# routed_anemo4.net
KiCad netlist of a schematic drawn in EAGLE
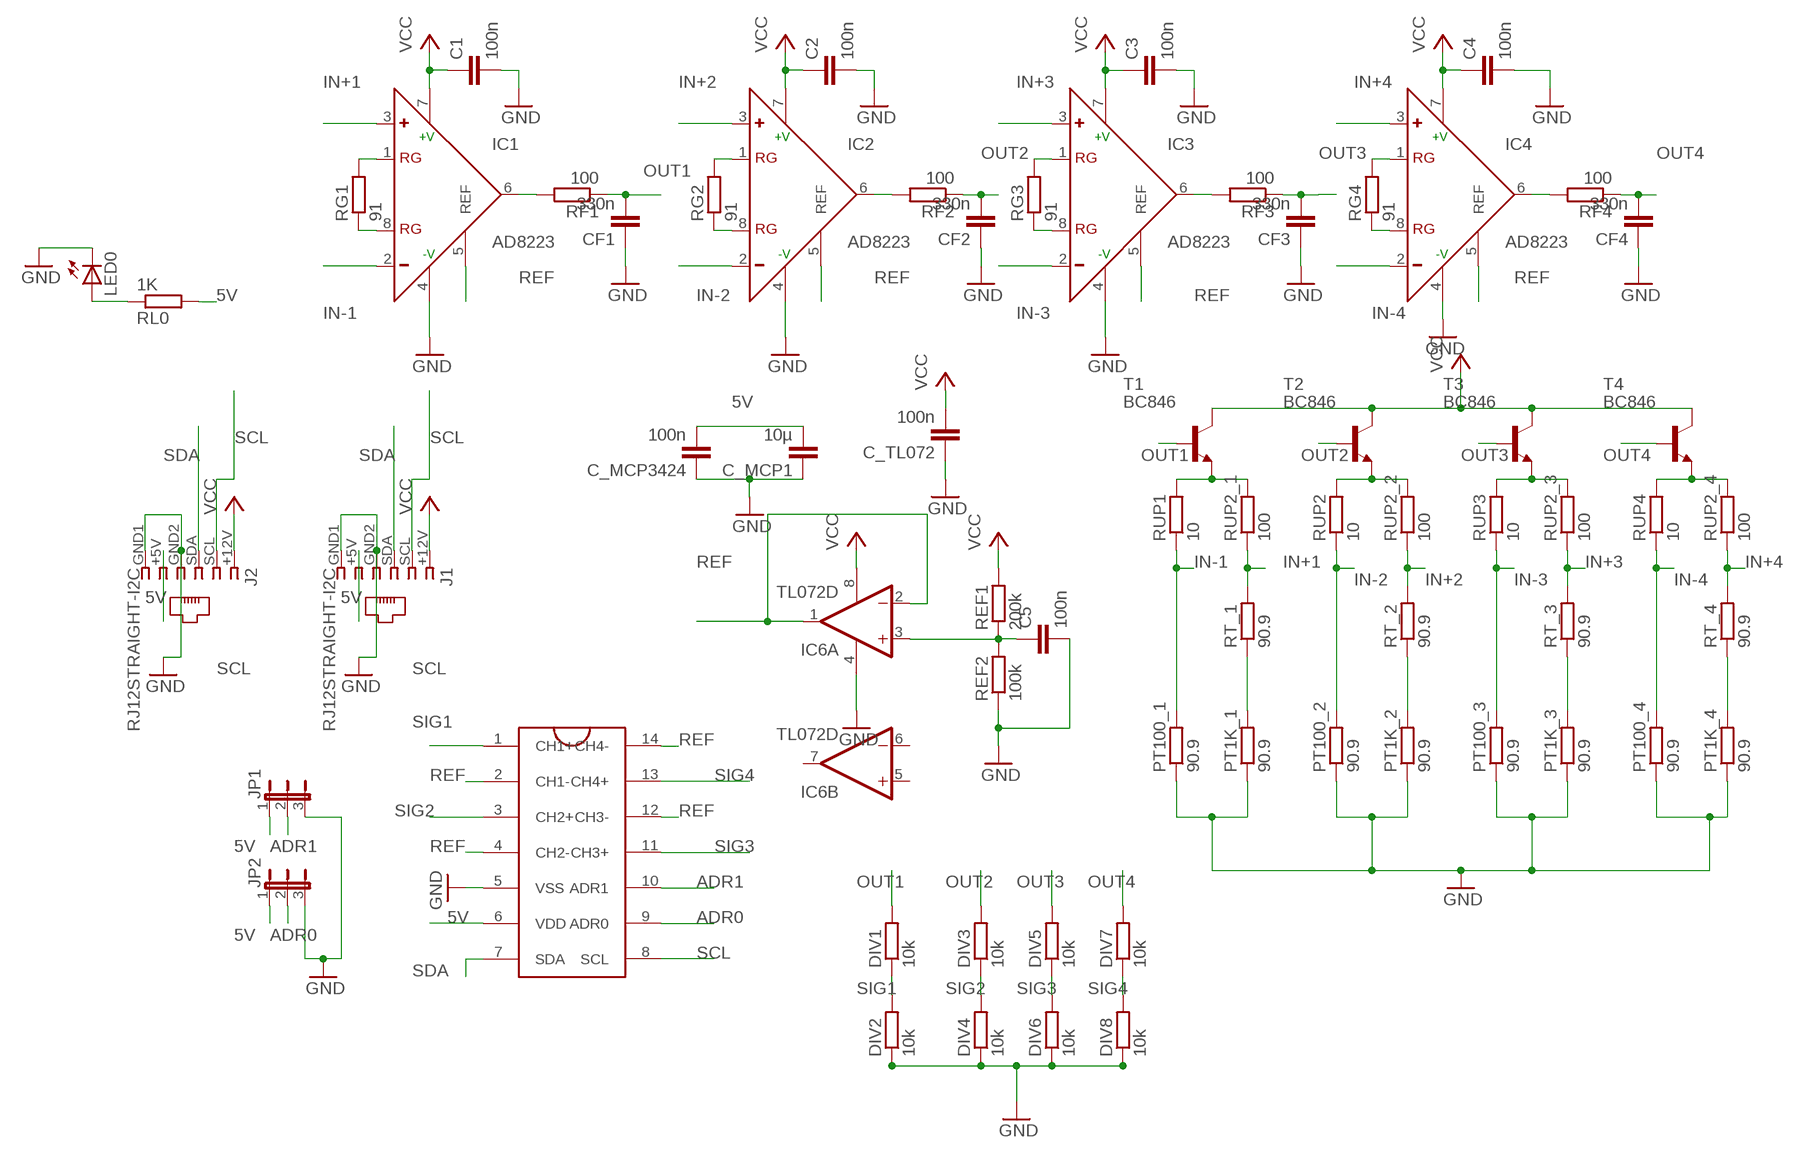
[diagram p0: schematic, sheet 1]

(export (version "E")
  (design (tool "Eeschema 10.0.6"))
  (components
    (comp (ref "C1")
      (value "100n")
      (footprint "eagle-import:C1206")
      (libsource (lib "eagle-import") (part "C-EUC1206"))
    )
    (comp (ref "C2")
      (value "100n")
      (footprint "eagle-import:C1206")
      (libsource (lib "eagle-import") (part "C-EUC1206"))
    )
    (comp (ref "C3")
      (value "100n")
      (footprint "eagle-import:C1206")
      (libsource (lib "eagle-import") (part "C-EUC1206"))
    )
    (comp (ref "C4")
      (value "100n")
      (footprint "eagle-import:C1206")
      (libsource (lib "eagle-import") (part "C-EUC1206"))
    )
    (comp (ref "C5")
      (value "100n")
      (footprint "eagle-import:C1206")
      (libsource (lib "eagle-import") (part "C-EUC1206"))
    )
    (comp (ref "CF1")
      (value "330n")
      (footprint "eagle-import:C1206")
      (libsource (lib "eagle-import") (part "C-EUC1206"))
    )
    (comp (ref "CF2")
      (value "330n")
      (footprint "eagle-import:C1206")
      (libsource (lib "eagle-import") (part "C-EUC1206"))
    )
    (comp (ref "CF3")
      (value "330n")
      (footprint "eagle-import:C1206")
      (libsource (lib "eagle-import") (part "C-EUC1206"))
    )
    (comp (ref "CF4")
      (value "330n")
      (footprint "eagle-import:C1206")
      (libsource (lib "eagle-import") (part "C-EUC1206"))
    )
    (comp (ref "C_MCP1")
      (value "10µ")
      (footprint "eagle-import:C1206")
      (libsource (lib "eagle-import") (part "C-EUC1206"))
    )
    (comp (ref "C_MCP3424")
      (value "100n")
      (footprint "eagle-import:C1206")
      (libsource (lib "eagle-import") (part "C-EUC1206"))
    )
    (comp (ref "C_TL072")
      (value "100n")
      (footprint "eagle-import:C1206")
      (libsource (lib "eagle-import") (part "C-EUC1206"))
    )
    (comp (ref "DIV1")
      (value "10k")
      (footprint "eagle-import:M1206")
      (libsource (lib "eagle-import") (part "R-EU_M1206"))
    )
    (comp (ref "DIV2")
      (value "10k")
      (footprint "eagle-import:M1206")
      (libsource (lib "eagle-import") (part "R-EU_M1206"))
    )
    (comp (ref "DIV3")
      (value "10k")
      (footprint "eagle-import:M1206")
      (libsource (lib "eagle-import") (part "R-EU_M1206"))
    )
    (comp (ref "DIV4")
      (value "10k")
      (footprint "eagle-import:M1206")
      (libsource (lib "eagle-import") (part "R-EU_M1206"))
    )
    (comp (ref "DIV5")
      (value "10k")
      (footprint "eagle-import:M1206")
      (libsource (lib "eagle-import") (part "R-EU_M1206"))
    )
    (comp (ref "DIV6")
      (value "10k")
      (footprint "eagle-import:M1206")
      (libsource (lib "eagle-import") (part "R-EU_M1206"))
    )
    (comp (ref "DIV7")
      (value "10k")
      (footprint "eagle-import:M1206")
      (libsource (lib "eagle-import") (part "R-EU_M1206"))
    )
    (comp (ref "DIV8")
      (value "10k")
      (footprint "eagle-import:M1206")
      (libsource (lib "eagle-import") (part "R-EU_M1206"))
    )
    (comp (ref "IC1")
      (value "AD8223")
      (footprint "eagle-import:SO8")
      (fields (field (name "MPN") "AD620AR"))
      (libsource (lib "eagle-import") (part "AD620R"))
    )
    (comp (ref "IC2")
      (value "AD8223")
      (footprint "eagle-import:SO8")
      (fields (field (name "MPN") "AD620AR"))
      (libsource (lib "eagle-import") (part "AD620R"))
    )
    (comp (ref "IC3")
      (value "AD8223")
      (footprint "eagle-import:SO8")
      (fields (field (name "MPN") "AD620AR"))
      (libsource (lib "eagle-import") (part "AD620R"))
    )
    (comp (ref "IC4")
      (value "AD8223")
      (footprint "eagle-import:SO8")
      (fields (field (name "MPN") "AD620AR"))
      (libsource (lib "eagle-import") (part "AD620R"))
    )
    (comp (ref "IC6")
      (value "TL072D")
      (footprint "eagle-import:SO08")
      (libsource (lib "eagle-import") (part "TL072D"))
    )
    (comp (ref "J1")
      (value "RJ12STRAIGHT-I2C")
      (footprint "eagle-import:RJ12-STRAIGHT-I2C")
      (libsource (lib "eagle-import") (part "RJ12STRAIGHT-I2C"))
    )
    (comp (ref "J2")
      (value "RJ12STRAIGHT-I2C")
      (footprint "eagle-import:RJ12-STRAIGHT-I2C")
      (libsource (lib "eagle-import") (part "RJ12STRAIGHT-I2C"))
    )
    (comp (ref "JP1")
      (value "JP2E")
      (footprint "eagle-import:JP2")
      (libsource (lib "eagle-import") (part "JP2E"))
    )
    (comp (ref "JP2")
      (value "JP2E")
      (footprint "eagle-import:JP2")
      (libsource (lib "eagle-import") (part "JP2E"))
    )
    (comp (ref "LED0")
      (value "LED1206")
      (footprint "eagle-import:LED-1206")
      (libsource (lib "eagle-import") (part "LED1206"))
    )
    (comp (ref "PT1K_1")
      (value "90.9")
      (footprint "eagle-import:M1206")
      (libsource (lib "eagle-import") (part "R-EU_M1206"))
    )
    (comp (ref "PT1K_2")
      (value "90.9")
      (footprint "eagle-import:M1206")
      (libsource (lib "eagle-import") (part "R-EU_M1206"))
    )
    (comp (ref "PT1K_3")
      (value "90.9")
      (footprint "eagle-import:M1206")
      (libsource (lib "eagle-import") (part "R-EU_M1206"))
    )
    (comp (ref "PT1K_4")
      (value "90.9")
      (footprint "eagle-import:M1206")
      (libsource (lib "eagle-import") (part "R-EU_M1206"))
    )
    (comp (ref "PT100_1")
      (value "90.9")
      (footprint "eagle-import:M1206")
      (libsource (lib "eagle-import") (part "R-EU_M1206"))
    )
    (comp (ref "PT100_2")
      (value "90.9")
      (footprint "eagle-import:M1206")
      (libsource (lib "eagle-import") (part "R-EU_M1206"))
    )
    (comp (ref "PT100_3")
      (value "90.9")
      (footprint "eagle-import:M1206")
      (libsource (lib "eagle-import") (part "R-EU_M1206"))
    )
    (comp (ref "PT100_4")
      (value "90.9")
      (footprint "eagle-import:M1206")
      (libsource (lib "eagle-import") (part "R-EU_M1206"))
    )
    (comp (ref "REF1")
      (value "200k")
      (footprint "eagle-import:M1206")
      (libsource (lib "eagle-import") (part "R-EU_M1206"))
    )
    (comp (ref "REF2")
      (value "100k")
      (footprint "eagle-import:M1206")
      (libsource (lib "eagle-import") (part "R-EU_M1206"))
    )
    (comp (ref "RF1")
      (value "100")
      (footprint "eagle-import:M1206")
      (libsource (lib "eagle-import") (part "R-EU_M1206"))
    )
    (comp (ref "RF2")
      (value "100")
      (footprint "eagle-import:M1206")
      (libsource (lib "eagle-import") (part "R-EU_M1206"))
    )
    (comp (ref "RF3")
      (value "100")
      (footprint "eagle-import:M1206")
      (libsource (lib "eagle-import") (part "R-EU_M1206"))
    )
    (comp (ref "RF4")
      (value "100")
      (footprint "eagle-import:M1206")
      (libsource (lib "eagle-import") (part "R-EU_M1206"))
    )
    (comp (ref "RG1")
      (value "91")
      (footprint "eagle-import:M1206")
      (libsource (lib "eagle-import") (part "R-EU_M1206"))
    )
    (comp (ref "RG2")
      (value "91")
      (footprint "eagle-import:M1206")
      (libsource (lib "eagle-import") (part "R-EU_M1206"))
    )
    (comp (ref "RG3")
      (value "91")
      (footprint "eagle-import:M1206")
      (libsource (lib "eagle-import") (part "R-EU_M1206"))
    )
    (comp (ref "RG4")
      (value "91")
      (footprint "eagle-import:M1206")
      (libsource (lib "eagle-import") (part "R-EU_M1206"))
    )
    (comp (ref "RL0")
      (value "1K")
      (footprint "eagle-import:M1206")
      (libsource (lib "eagle-import") (part "R-EU_M1206"))
    )
    (comp (ref "RT_1")
      (value "90.9")
      (footprint "eagle-import:M1206")
      (libsource (lib "eagle-import") (part "R-EU_M1206"))
    )
    (comp (ref "RT_2")
      (value "90.9")
      (footprint "eagle-import:M1206")
      (libsource (lib "eagle-import") (part "R-EU_M1206"))
    )
    (comp (ref "RT_3")
      (value "90.9")
      (footprint "eagle-import:M1206")
      (libsource (lib "eagle-import") (part "R-EU_M1206"))
    )
    (comp (ref "RT_4")
      (value "90.9")
      (footprint "eagle-import:M1206")
      (libsource (lib "eagle-import") (part "R-EU_M1206"))
    )
    (comp (ref "RUP1")
      (value "10")
      (footprint "eagle-import:M1206")
      (libsource (lib "eagle-import") (part "R-EU_M1206"))
    )
    (comp (ref "RUP2")
      (value "10")
      (footprint "eagle-import:M1206")
      (libsource (lib "eagle-import") (part "R-EU_M1206"))
    )
    (comp (ref "RUP2_1")
      (value "100")
      (footprint "eagle-import:M1206")
      (libsource (lib "eagle-import") (part "R-EU_M1206"))
    )
    (comp (ref "RUP2_2")
      (value "100")
      (footprint "eagle-import:M1206")
      (libsource (lib "eagle-import") (part "R-EU_M1206"))
    )
    (comp (ref "RUP2_3")
      (value "100")
      (footprint "eagle-import:M1206")
      (libsource (lib "eagle-import") (part "R-EU_M1206"))
    )
    (comp (ref "RUP2_4")
      (value "100")
      (footprint "eagle-import:M1206")
      (libsource (lib "eagle-import") (part "R-EU_M1206"))
    )
    (comp (ref "RUP3")
      (value "10")
      (footprint "eagle-import:M1206")
      (libsource (lib "eagle-import") (part "R-EU_M1206"))
    )
    (comp (ref "RUP4")
      (value "10")
      (footprint "eagle-import:M1206")
      (libsource (lib "eagle-import") (part "R-EU_M1206"))
    )
    (comp (ref "T1")
      (value "BC846")
      (footprint "eagle-import:SOT23")
      (libsource (lib "eagle-import") (part "BC846"))
    )
    (comp (ref "T2")
      (value "BC846")
      (footprint "eagle-import:SOT23")
      (libsource (lib "eagle-import") (part "BC846"))
    )
    (comp (ref "T3")
      (value "BC846")
      (footprint "eagle-import:SOT23")
      (libsource (lib "eagle-import") (part "BC846"))
    )
    (comp (ref "T4")
      (value "BC846")
      (footprint "eagle-import:SOT23")
      (libsource (lib "eagle-import") (part "BC846"))
    )
    (comp (ref "U$1")
      (value "MCP3424(SO14)")
      (footprint "eagle-import:14LDSOIC")
      (libsource (lib "eagle-import") (part "MCP3424(SO14)"))
    )
  )
  (nets
    (net (code "1") (name "/5V") (class "Default")
      (node (ref "C_MCP1") (pin "2") (pinfunction "2_2") (pintype "passive"))
      (node (ref "C_MCP3424") (pin "2") (pinfunction "2_2") (pintype "passive"))
      (node (ref "J1") (pin "+5V") (pinfunction "5_+5V") (pintype "bidirectional"))
      (node (ref "J2") (pin "+5V") (pinfunction "5_+5V") (pintype "bidirectional"))
      (node (ref "JP1") (pin "1") (pinfunction "1_1") (pintype "passive"))
      (node (ref "JP2") (pin "1") (pinfunction "1_1") (pintype "passive"))
      (node (ref "RL0") (pin "2") (pinfunction "2_2") (pintype "passive"))
      (node (ref "U$1") (pin "6") (pinfunction "VDD_6") (pintype "bidirectional"))
    )
    (net (code "2") (name "/ADR0") (class "Default")
      (node (ref "JP2") (pin "2") (pinfunction "2_2") (pintype "passive"))
      (node (ref "U$1") (pin "9") (pinfunction "ADR0_9") (pintype "bidirectional"))
    )
    (net (code "3") (name "/ADR1") (class "Default")
      (node (ref "JP1") (pin "2") (pinfunction "2_2") (pintype "passive"))
      (node (ref "U$1") (pin "10") (pinfunction "ADR1_10") (pintype "bidirectional"))
    )
    (net (code "4") (name "/IN+1") (class "Default")
      (node (ref "IC1") (pin "3") (pinfunction "+_3") (pintype "input"))
      (node (ref "RT_1") (pin "2") (pinfunction "2_2") (pintype "passive"))
      (node (ref "RUP2_1") (pin "1") (pinfunction "1_1") (pintype "passive"))
    )
    (net (code "5") (name "/IN+2") (class "Default")
      (node (ref "IC2") (pin "3") (pinfunction "+_3") (pintype "input"))
      (node (ref "RT_2") (pin "2") (pinfunction "2_2") (pintype "passive"))
      (node (ref "RUP2_2") (pin "1") (pinfunction "1_1") (pintype "passive"))
    )
    (net (code "6") (name "/IN+3") (class "Default")
      (node (ref "IC3") (pin "3") (pinfunction "+_3") (pintype "input"))
      (node (ref "RT_3") (pin "2") (pinfunction "2_2") (pintype "passive"))
      (node (ref "RUP2_3") (pin "1") (pinfunction "1_1") (pintype "passive"))
    )
    (net (code "7") (name "/IN+4") (class "Default")
      (node (ref "IC4") (pin "3") (pinfunction "+_3") (pintype "input"))
      (node (ref "RT_4") (pin "2") (pinfunction "2_2") (pintype "passive"))
      (node (ref "RUP2_4") (pin "1") (pinfunction "1_1") (pintype "passive"))
    )
    (net (code "8") (name "/IN-1") (class "Default")
      (node (ref "IC1") (pin "2") (pinfunction "-_2") (pintype "input"))
      (node (ref "PT100_1") (pin "2") (pinfunction "2_2") (pintype "passive"))
      (node (ref "RUP1") (pin "1") (pinfunction "1_1") (pintype "passive"))
    )
    (net (code "9") (name "/IN-2") (class "Default")
      (node (ref "IC2") (pin "2") (pinfunction "-_2") (pintype "input"))
      (node (ref "PT100_2") (pin "2") (pinfunction "2_2") (pintype "passive"))
      (node (ref "RUP2") (pin "1") (pinfunction "1_1") (pintype "passive"))
    )
    (net (code "10") (name "/IN-3") (class "Default")
      (node (ref "IC3") (pin "2") (pinfunction "-_2") (pintype "input"))
      (node (ref "PT100_3") (pin "2") (pinfunction "2_2") (pintype "passive"))
      (node (ref "RUP3") (pin "1") (pinfunction "1_1") (pintype "passive"))
    )
    (net (code "11") (name "/IN-4") (class "Default")
      (node (ref "IC4") (pin "2") (pinfunction "-_2") (pintype "input"))
      (node (ref "PT100_4") (pin "2") (pinfunction "2_2") (pintype "passive"))
      (node (ref "RUP4") (pin "1") (pinfunction "1_1") (pintype "passive"))
    )
    (net (code "12") (name "/OUT1") (class "Default")
      (node (ref "CF1") (pin "2") (pinfunction "2_2") (pintype "passive"))
      (node (ref "DIV1") (pin "2") (pinfunction "2_2") (pintype "passive"))
      (node (ref "RF1") (pin "1") (pinfunction "1_1") (pintype "passive"))
      (node (ref "T1") (pin "1") (pinfunction "B_1") (pintype "passive"))
    )
    (net (code "13") (name "/OUT2") (class "Default")
      (node (ref "CF2") (pin "2") (pinfunction "2_2") (pintype "passive"))
      (node (ref "DIV3") (pin "2") (pinfunction "2_2") (pintype "passive"))
      (node (ref "RF2") (pin "1") (pinfunction "1_1") (pintype "passive"))
      (node (ref "T2") (pin "1") (pinfunction "B_1") (pintype "passive"))
    )
    (net (code "14") (name "/OUT3") (class "Default")
      (node (ref "CF3") (pin "2") (pinfunction "2_2") (pintype "passive"))
      (node (ref "DIV5") (pin "2") (pinfunction "2_2") (pintype "passive"))
      (node (ref "RF3") (pin "1") (pinfunction "1_1") (pintype "passive"))
      (node (ref "T3") (pin "1") (pinfunction "B_1") (pintype "passive"))
    )
    (net (code "15") (name "/OUT4") (class "Default")
      (node (ref "CF4") (pin "2") (pinfunction "2_2") (pintype "passive"))
      (node (ref "DIV7") (pin "2") (pinfunction "2_2") (pintype "passive"))
      (node (ref "RF4") (pin "1") (pinfunction "1_1") (pintype "passive"))
      (node (ref "T4") (pin "1") (pinfunction "B_1") (pintype "passive"))
    )
    (net (code "16") (name "/REF") (class "Default")
      (node (ref "IC1") (pin "5") (pinfunction "REF_5") (pintype "passive"))
      (node (ref "IC2") (pin "5") (pinfunction "REF_5") (pintype "passive"))
      (node (ref "IC3") (pin "5") (pinfunction "REF_5") (pintype "passive"))
      (node (ref "IC4") (pin "5") (pinfunction "REF_5") (pintype "passive"))
      (node (ref "IC6") (pin "1") (pinfunction "OUT_1") (pintype "output"))
      (node (ref "IC6") (pin "2") (pinfunction "-IN_2") (pintype "input"))
      (node (ref "U$1") (pin "12") (pinfunction "CH3-_12") (pintype "bidirectional"))
      (node (ref "U$1") (pin "14") (pinfunction "CH4-_14") (pintype "bidirectional"))
      (node (ref "U$1") (pin "2") (pinfunction "CH1-_2") (pintype "bidirectional"))
      (node (ref "U$1") (pin "4") (pinfunction "CH2-_4") (pintype "bidirectional"))
    )
    (net (code "17") (name "/SCL") (class "Default")
      (node (ref "J1") (pin "SCL") (pinfunction "2_SCL") (pintype "bidirectional"))
      (node (ref "J2") (pin "SCL") (pinfunction "2_SCL") (pintype "bidirectional"))
      (node (ref "U$1") (pin "8") (pinfunction "SCL_8") (pintype "bidirectional"))
    )
    (net (code "18") (name "/SDA") (class "Default")
      (node (ref "J1") (pin "SDA") (pinfunction "3_SDA") (pintype "bidirectional"))
      (node (ref "J2") (pin "SDA") (pinfunction "3_SDA") (pintype "bidirectional"))
      (node (ref "U$1") (pin "7") (pinfunction "SDA_7") (pintype "bidirectional"))
    )
    (net (code "19") (name "/SIG1") (class "Default")
      (node (ref "DIV1") (pin "1") (pinfunction "1_1") (pintype "passive"))
      (node (ref "DIV2") (pin "2") (pinfunction "2_2") (pintype "passive"))
      (node (ref "U$1") (pin "1") (pinfunction "CH1+_1") (pintype "bidirectional"))
    )
    (net (code "20") (name "/SIG2") (class "Default")
      (node (ref "DIV3") (pin "1") (pinfunction "1_1") (pintype "passive"))
      (node (ref "DIV4") (pin "2") (pinfunction "2_2") (pintype "passive"))
      (node (ref "U$1") (pin "3") (pinfunction "CH2+_3") (pintype "bidirectional"))
    )
    (net (code "21") (name "/SIG3") (class "Default")
      (node (ref "DIV5") (pin "1") (pinfunction "1_1") (pintype "passive"))
      (node (ref "DIV6") (pin "2") (pinfunction "2_2") (pintype "passive"))
      (node (ref "U$1") (pin "11") (pinfunction "CH3+_11") (pintype "bidirectional"))
    )
    (net (code "22") (name "/SIG4") (class "Default")
      (node (ref "DIV7") (pin "1") (pinfunction "1_1") (pintype "passive"))
      (node (ref "DIV8") (pin "2") (pinfunction "2_2") (pintype "passive"))
      (node (ref "U$1") (pin "13") (pinfunction "CH4+_13") (pintype "bidirectional"))
    )
    (net (code "23") (name "GND") (class "Default")
      (node (ref "C1") (pin "2") (pinfunction "2_2") (pintype "passive"))
      (node (ref "C2") (pin "2") (pinfunction "2_2") (pintype "passive"))
      (node (ref "C3") (pin "2") (pinfunction "2_2") (pintype "passive"))
      (node (ref "C4") (pin "2") (pinfunction "2_2") (pintype "passive"))
      (node (ref "C5") (pin "2") (pinfunction "2_2") (pintype "passive"))
      (node (ref "CF1") (pin "1") (pinfunction "1_1") (pintype "passive"))
      (node (ref "CF2") (pin "1") (pinfunction "1_1") (pintype "passive"))
      (node (ref "CF3") (pin "1") (pinfunction "1_1") (pintype "passive"))
      (node (ref "CF4") (pin "1") (pinfunction "1_1") (pintype "passive"))
      (node (ref "C_MCP1") (pin "1") (pinfunction "1_1") (pintype "passive"))
      (node (ref "C_MCP3424") (pin "1") (pinfunction "1_1") (pintype "passive"))
      (node (ref "C_TL072") (pin "1") (pinfunction "1_1") (pintype "passive"))
      (node (ref "DIV2") (pin "1") (pinfunction "1_1") (pintype "passive"))
      (node (ref "DIV4") (pin "1") (pinfunction "1_1") (pintype "passive"))
      (node (ref "DIV6") (pin "1") (pinfunction "1_1") (pintype "passive"))
      (node (ref "DIV8") (pin "1") (pinfunction "1_1") (pintype "passive"))
      (node (ref "IC1") (pin "4") (pinfunction "-V_4") (pintype "power_in"))
      (node (ref "IC2") (pin "4") (pinfunction "-V_4") (pintype "power_in"))
      (node (ref "IC3") (pin "4") (pinfunction "-V_4") (pintype "power_in"))
      (node (ref "IC4") (pin "4") (pinfunction "-V_4") (pintype "power_in"))
      (node (ref "IC6") (pin "4") (pinfunction "V-_4") (pintype "power_in"))
      (node (ref "J1") (pin "GND1") (pinfunction "6_GND1") (pintype "bidirectional"))
      (node (ref "J1") (pin "GND2") (pinfunction "4_GND2") (pintype "bidirectional"))
      (node (ref "J2") (pin "GND1") (pinfunction "6_GND1") (pintype "bidirectional"))
      (node (ref "J2") (pin "GND2") (pinfunction "4_GND2") (pintype "bidirectional"))
      (node (ref "JP1") (pin "3") (pinfunction "3_3") (pintype "passive"))
      (node (ref "JP2") (pin "3") (pinfunction "3_3") (pintype "passive"))
      (node (ref "LED0") (pin "C") (pinfunction "C_C") (pintype "passive"))
      (node (ref "PT100_1") (pin "1") (pinfunction "1_1") (pintype "passive"))
      (node (ref "PT100_2") (pin "1") (pinfunction "1_1") (pintype "passive"))
      (node (ref "PT100_3") (pin "1") (pinfunction "1_1") (pintype "passive"))
      (node (ref "PT100_4") (pin "1") (pinfunction "1_1") (pintype "passive"))
      (node (ref "PT1K_1") (pin "1") (pinfunction "1_1") (pintype "passive"))
      (node (ref "PT1K_2") (pin "1") (pinfunction "1_1") (pintype "passive"))
      (node (ref "PT1K_3") (pin "1") (pinfunction "1_1") (pintype "passive"))
      (node (ref "PT1K_4") (pin "1") (pinfunction "1_1") (pintype "passive"))
      (node (ref "REF2") (pin "1") (pinfunction "1_1") (pintype "passive"))
      (node (ref "U$1") (pin "5") (pinfunction "VSS_5") (pintype "bidirectional"))
    )
    (net (code "24") (name "Net-(IC1-OUT)") (class "Default")
      (node (ref "IC1") (pin "6") (pinfunction "OUT_6") (pintype "output"))
      (node (ref "RF1") (pin "2") (pinfunction "2_2") (pintype "passive"))
    )
    (net (code "25") (name "Net-(IC1-RG-Pad1)") (class "Default")
      (node (ref "IC1") (pin "1") (pinfunction "RG_1") (pintype "passive"))
      (node (ref "RG1") (pin "2") (pinfunction "2_2") (pintype "passive"))
    )
    (net (code "26") (name "Net-(IC1-RG-Pad8)") (class "Default")
      (node (ref "IC1") (pin "8") (pinfunction "RG_8") (pintype "passive"))
      (node (ref "RG1") (pin "1") (pinfunction "1_1") (pintype "passive"))
    )
    (net (code "27") (name "Net-(IC2-OUT)") (class "Default")
      (node (ref "IC2") (pin "6") (pinfunction "OUT_6") (pintype "output"))
      (node (ref "RF2") (pin "2") (pinfunction "2_2") (pintype "passive"))
    )
    (net (code "28") (name "Net-(IC2-RG-Pad1)") (class "Default")
      (node (ref "IC2") (pin "1") (pinfunction "RG_1") (pintype "passive"))
      (node (ref "RG2") (pin "2") (pinfunction "2_2") (pintype "passive"))
    )
    (net (code "29") (name "Net-(IC2-RG-Pad8)") (class "Default")
      (node (ref "IC2") (pin "8") (pinfunction "RG_8") (pintype "passive"))
      (node (ref "RG2") (pin "1") (pinfunction "1_1") (pintype "passive"))
    )
    (net (code "30") (name "Net-(IC3-OUT)") (class "Default")
      (node (ref "IC3") (pin "6") (pinfunction "OUT_6") (pintype "output"))
      (node (ref "RF3") (pin "2") (pinfunction "2_2") (pintype "passive"))
    )
    (net (code "31") (name "Net-(IC3-RG-Pad1)") (class "Default")
      (node (ref "IC3") (pin "1") (pinfunction "RG_1") (pintype "passive"))
      (node (ref "RG3") (pin "2") (pinfunction "2_2") (pintype "passive"))
    )
    (net (code "32") (name "Net-(IC3-RG-Pad8)") (class "Default")
      (node (ref "IC3") (pin "8") (pinfunction "RG_8") (pintype "passive"))
      (node (ref "RG3") (pin "1") (pinfunction "1_1") (pintype "passive"))
    )
    (net (code "33") (name "Net-(IC4-OUT)") (class "Default")
      (node (ref "IC4") (pin "6") (pinfunction "OUT_6") (pintype "output"))
      (node (ref "RF4") (pin "2") (pinfunction "2_2") (pintype "passive"))
    )
    (net (code "34") (name "Net-(IC4-RG-Pad1)") (class "Default")
      (node (ref "IC4") (pin "1") (pinfunction "RG_1") (pintype "passive"))
      (node (ref "RG4") (pin "2") (pinfunction "2_2") (pintype "passive"))
    )
    (net (code "35") (name "Net-(IC4-RG-Pad8)") (class "Default")
      (node (ref "IC4") (pin "8") (pinfunction "RG_8") (pintype "passive"))
      (node (ref "RG4") (pin "1") (pinfunction "1_1") (pintype "passive"))
    )
    (net (code "36") (name "Net-(IC6A-+IN)") (class "Default")
      (node (ref "C5") (pin "1") (pinfunction "1_1") (pintype "passive"))
      (node (ref "IC6") (pin "3") (pinfunction "+IN_3") (pintype "input"))
      (node (ref "REF1") (pin "1") (pinfunction "1_1") (pintype "passive"))
      (node (ref "REF2") (pin "2") (pinfunction "2_2") (pintype "passive"))
    )
    (net (code "37") (name "Net-(LED0-PadA)") (class "Default")
      (node (ref "LED0") (pin "A") (pinfunction "A_A") (pintype "passive"))
      (node (ref "RL0") (pin "1") (pinfunction "1_1") (pintype "passive"))
    )
    (net (code "38") (name "Net-(PT1K_1-Pad2)") (class "Default")
      (node (ref "PT1K_1") (pin "2") (pinfunction "2_2") (pintype "passive"))
      (node (ref "RT_1") (pin "1") (pinfunction "1_1") (pintype "passive"))
    )
    (net (code "39") (name "Net-(PT1K_2-Pad2)") (class "Default")
      (node (ref "PT1K_2") (pin "2") (pinfunction "2_2") (pintype "passive"))
      (node (ref "RT_2") (pin "1") (pinfunction "1_1") (pintype "passive"))
    )
    (net (code "40") (name "Net-(PT1K_3-Pad2)") (class "Default")
      (node (ref "PT1K_3") (pin "2") (pinfunction "2_2") (pintype "passive"))
      (node (ref "RT_3") (pin "1") (pinfunction "1_1") (pintype "passive"))
    )
    (net (code "41") (name "Net-(PT1K_4-Pad2)") (class "Default")
      (node (ref "PT1K_4") (pin "2") (pinfunction "2_2") (pintype "passive"))
      (node (ref "RT_4") (pin "1") (pinfunction "1_1") (pintype "passive"))
    )
    (net (code "42") (name "Net-(T1-E)") (class "Default")
      (node (ref "RUP1") (pin "2") (pinfunction "2_2") (pintype "passive"))
      (node (ref "RUP2_1") (pin "2") (pinfunction "2_2") (pintype "passive"))
      (node (ref "T1") (pin "2") (pinfunction "E_2") (pintype "passive"))
    )
    (net (code "43") (name "Net-(T2-E)") (class "Default")
      (node (ref "RUP2") (pin "2") (pinfunction "2_2") (pintype "passive"))
      (node (ref "RUP2_2") (pin "2") (pinfunction "2_2") (pintype "passive"))
      (node (ref "T2") (pin "2") (pinfunction "E_2") (pintype "passive"))
    )
    (net (code "44") (name "Net-(T3-E)") (class "Default")
      (node (ref "RUP2_3") (pin "2") (pinfunction "2_2") (pintype "passive"))
      (node (ref "RUP3") (pin "2") (pinfunction "2_2") (pintype "passive"))
      (node (ref "T3") (pin "2") (pinfunction "E_2") (pintype "passive"))
    )
    (net (code "45") (name "Net-(T4-E)") (class "Default")
      (node (ref "RUP2_4") (pin "2") (pinfunction "2_2") (pintype "passive"))
      (node (ref "RUP4") (pin "2") (pinfunction "2_2") (pintype "passive"))
      (node (ref "T4") (pin "2") (pinfunction "E_2") (pintype "passive"))
    )
    (net (code "46") (name "VCC") (class "Default")
      (node (ref "C1") (pin "1") (pinfunction "1_1") (pintype "passive"))
      (node (ref "C2") (pin "1") (pinfunction "1_1") (pintype "passive"))
      (node (ref "C3") (pin "1") (pinfunction "1_1") (pintype "passive"))
      (node (ref "C4") (pin "1") (pinfunction "1_1") (pintype "passive"))
      (node (ref "C_TL072") (pin "2") (pinfunction "2_2") (pintype "passive"))
      (node (ref "IC1") (pin "7") (pinfunction "+V_7") (pintype "power_in"))
      (node (ref "IC2") (pin "7") (pinfunction "+V_7") (pintype "power_in"))
      (node (ref "IC3") (pin "7") (pinfunction "+V_7") (pintype "power_in"))
      (node (ref "IC4") (pin "7") (pinfunction "+V_7") (pintype "power_in"))
      (node (ref "IC6") (pin "8") (pinfunction "V+_8") (pintype "power_in"))
      (node (ref "J1") (pin "+12V") (pinfunction "1_+12V") (pintype "bidirectional"))
      (node (ref "J2") (pin "+12V") (pinfunction "1_+12V") (pintype "bidirectional"))
      (node (ref "REF1") (pin "2") (pinfunction "2_2") (pintype "passive"))
      (node (ref "T1") (pin "3") (pinfunction "C_3") (pintype "passive"))
      (node (ref "T2") (pin "3") (pinfunction "C_3") (pintype "passive"))
      (node (ref "T3") (pin "3") (pinfunction "C_3") (pintype "passive"))
      (node (ref "T4") (pin "3") (pinfunction "C_3") (pintype "passive"))
    )
    (net (code "47") (name "unconnected-(IC6B-+IN-Pad5)") (class "Default")
      (node (ref "IC6") (pin "5") (pinfunction "+IN_5") (pintype "input"))
    )
    (net (code "48") (name "unconnected-(IC6B--IN-Pad6)") (class "Default")
      (node (ref "IC6") (pin "6") (pinfunction "-IN_6") (pintype "input"))
    )
    (net (code "49") (name "unconnected-(IC6B-OUT-Pad7)") (class "Default")
      (node (ref "IC6") (pin "7") (pinfunction "OUT_7") (pintype "output"))
    )
  )
)
